# Auxilary.net
KiCad netlist of a schematic drawn in Altium Designer
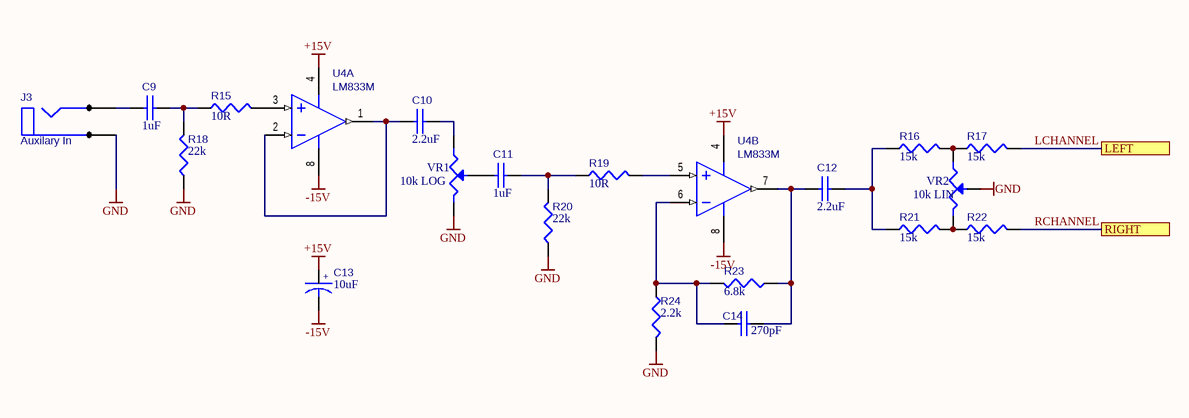
[diagram p0: Auxilary.SchDoc]

(export (version "E")
  (design (tool "Eeschema 10.0.6"))
  (components
    (comp (ref "C9")
      (value "1uF")
      (footprint "RB.2/.4-NP")
      (description "Capacitor")
      (libsource (lib "*") (part "CAP"))
    )
    (comp (ref "C10")
      (value "2.2uF")
      (footprint "RB.2/.4-NP")
      (description "Capacitor")
      (libsource (lib "*") (part "CAP"))
    )
    (comp (ref "C11")
      (value "1uF")
      (footprint "RB.2/.4-NP")
      (description "Capacitor")
      (libsource (lib "*") (part "CAP"))
    )
    (comp (ref "C12")
      (value "2.2uF")
      (footprint "RB.2/.4-NP")
      (description "Capacitor")
      (libsource (lib "*") (part "CAP"))
    )
    (comp (ref "C13")
      (value "10uF")
      (footprint "RB.2/.4")
      (description "Bi-Polar Capacitor")
      (libsource (lib "*") (part "CAPACITOR POL"))
    )
    (comp (ref "C14")
      (value "270pF")
      (footprint "RAD0.2")
      (description "Capacitor")
      (libsource (lib "*") (part "CAP"))
    )
    (comp (ref "J3")
      (value "Auxilary In")
      (footprint "JACK-6.25MM")
      (libsource (lib "*") (part "PHONEJACK MONO"))
    )
    (comp (ref "R15")
      (value "10R")
      (footprint "AXIAL0.4")
      (description "Resistor")
      (libsource (lib "") (part "RES1_1"))
    )
    (comp (ref "R16")
      (value "15k")
      (footprint "AXIAL0.4")
      (description "Resistor")
      (libsource (lib "") (part "RES1_1"))
    )
    (comp (ref "R17")
      (value "15k")
      (footprint "AXIAL0.4")
      (description "Resistor")
      (libsource (lib "") (part "RES1_1"))
    )
    (comp (ref "R18")
      (value "22k")
      (footprint "AXIAL0.4")
      (description "Resistor")
      (libsource (lib "") (part "RES1_2"))
    )
    (comp (ref "R19")
      (value "10R")
      (footprint "AXIAL0.4")
      (description "Resistor")
      (libsource (lib "") (part "RES1_1"))
    )
    (comp (ref "R20")
      (value "22k")
      (footprint "AXIAL0.4")
      (description "Resistor")
      (libsource (lib "") (part "RES1_2"))
    )
    (comp (ref "R21")
      (value "15k")
      (footprint "AXIAL0.4")
      (description "Resistor")
      (libsource (lib "") (part "RES1_1"))
    )
    (comp (ref "R22")
      (value "15k")
      (footprint "AXIAL0.4")
      (description "Resistor")
      (libsource (lib "") (part "RES1_1"))
    )
    (comp (ref "R23")
      (value "6.8k")
      (footprint "AXIAL0.4")
      (description "Resistor")
      (libsource (lib "*") (part "RES1"))
    )
    (comp (ref "R24")
      (value "2.2k")
      (footprint "AXIAL0.4")
      (description "Resistor")
      (libsource (lib "") (part "RES1_3"))
    )
    (comp (ref "U4")
      (value "LM833M")
      (footprint "DIP8")
      (description "Fast Settling Dual Operational Amplifier")
      (libsource (lib "*") (part "LM833M"))
    )
    (comp (ref "VR1")
      (value "10k LOG")
      (footprint "POT - 24MM")
      (description "Potentiometer")
      (libsource (lib "*") (part "POT1"))
    )
    (comp (ref "VR2")
      (value "10k LIN")
      (footprint "POT - 24MM")
      (description "Potentiometer")
      (libsource (lib "*") (part "POT1"))
    )
  )
  (nets
    (net (code "1") (name "+15V") (class "Default")
      (node (ref "C13") (pin "1") (pinfunction "1_1") (pintype "passive"))
      (node (ref "U4") (pin "4") (pinfunction "V-_4") (pintype "power_in"))
    )
    (net (code "2") (name "-15V") (class "Default")
      (node (ref "C13") (pin "2") (pinfunction "2_2") (pintype "passive"))
      (node (ref "U4") (pin "8") (pinfunction "V+_8") (pintype "power_in"))
    )
    (net (code "3") (name "/LCHANNEL") (class "Default")
      (node (ref "R17") (pin "2") (pinfunction "2_2") (pintype "passive"))
    )
    (net (code "4") (name "/RCHANNEL") (class "Default")
      (node (ref "R22") (pin "2") (pinfunction "2_2") (pintype "passive"))
    )
    (net (code "5") (name "GND") (class "Default")
      (node (ref "J3") (pin "3") (pinfunction "C_3") (pintype "passive"))
      (node (ref "R18") (pin "1") (pinfunction "1_1") (pintype "passive"))
      (node (ref "R20") (pin "1") (pinfunction "1_1") (pintype "passive"))
      (node (ref "R24") (pin "2") (pinfunction "2_2") (pintype "passive"))
      (node (ref "VR1") (pin "3") (pinfunction "3_3") (pintype "passive"))
      (node (ref "VR2") (pin "2") (pinfunction "W_2") (pintype "passive"))
    )
    (net (code "6") (name "Net-(C9-Pad2)") (class "Default")
      (node (ref "C9") (pin "2") (pinfunction "2_2") (pintype "passive"))
      (node (ref "R15") (pin "1") (pinfunction "1_1") (pintype "passive"))
      (node (ref "R18") (pin "2") (pinfunction "2_2") (pintype "passive"))
    )
    (net (code "7") (name "Net-(C10-Pad2)") (class "Default")
      (node (ref "C10") (pin "2") (pinfunction "2_2") (pintype "passive"))
      (node (ref "VR1") (pin "1") (pinfunction "1_1") (pintype "passive"))
    )
    (net (code "8") (name "Net-(C11-Pad2)") (class "Default")
      (node (ref "C11") (pin "2") (pinfunction "2_2") (pintype "passive"))
      (node (ref "R19") (pin "1") (pinfunction "1_1") (pintype "passive"))
      (node (ref "R20") (pin "2") (pinfunction "2_2") (pintype "passive"))
    )
    (net (code "9") (name "Net-(C12-Pad2)") (class "Default")
      (node (ref "C12") (pin "2") (pinfunction "2_2") (pintype "passive"))
      (node (ref "R16") (pin "1") (pinfunction "1_1") (pintype "passive"))
      (node (ref "R21") (pin "1") (pinfunction "1_1") (pintype "passive"))
    )
    (net (code "10") (name "Net-(J3-A)") (class "Default")
      (node (ref "C9") (pin "1") (pinfunction "1_1") (pintype "passive"))
      (node (ref "J3") (pin "1") (pinfunction "A_1") (pintype "passive"))
    )
    (net (code "11") (name "Net-(R16-Pad2)") (class "Default")
      (node (ref "R16") (pin "2") (pinfunction "2_2") (pintype "passive"))
      (node (ref "R17") (pin "1") (pinfunction "1_1") (pintype "passive"))
      (node (ref "VR2") (pin "1") (pinfunction "1_1") (pintype "passive"))
    )
    (net (code "12") (name "Net-(R21-Pad2)") (class "Default")
      (node (ref "R21") (pin "2") (pinfunction "2_2") (pintype "passive"))
      (node (ref "R22") (pin "1") (pinfunction "1_1") (pintype "passive"))
      (node (ref "VR2") (pin "3") (pinfunction "3_3") (pintype "passive"))
    )
    (net (code "13") (name "Net-(U4A-IN1+)") (class "Default")
      (node (ref "R15") (pin "2") (pinfunction "2_2") (pintype "passive"))
      (node (ref "U4") (pin "3") (pinfunction "IN1+_3") (pintype "input"))
    )
    (net (code "14") (name "Net-(U4A-IN1-)") (class "Default")
      (node (ref "C10") (pin "1") (pinfunction "1_1") (pintype "passive"))
      (node (ref "U4") (pin "1") (pinfunction "OUT1_1") (pintype "output"))
      (node (ref "U4") (pin "2") (pinfunction "IN1-_2") (pintype "input"))
    )
    (net (code "15") (name "Net-(U4B-IN2+)") (class "Default")
      (node (ref "R19") (pin "2") (pinfunction "2_2") (pintype "passive"))
      (node (ref "U4") (pin "5") (pinfunction "IN2+_5") (pintype "input"))
    )
    (net (code "16") (name "Net-(U4B-IN2-)") (class "Default")
      (node (ref "C14") (pin "1") (pinfunction "1_1") (pintype "passive"))
      (node (ref "R23") (pin "2") (pinfunction "2_2") (pintype "passive"))
      (node (ref "R24") (pin "1") (pinfunction "1_1") (pintype "passive"))
      (node (ref "U4") (pin "6") (pinfunction "IN2-_6") (pintype "input"))
    )
    (net (code "17") (name "Net-(U4B-OUT2)") (class "Default")
      (node (ref "C12") (pin "1") (pinfunction "1_1") (pintype "passive"))
      (node (ref "C14") (pin "2") (pinfunction "2_2") (pintype "passive"))
      (node (ref "R23") (pin "1") (pinfunction "1_1") (pintype "passive"))
      (node (ref "U4") (pin "7") (pinfunction "OUT2_7") (pintype "output"))
    )
    (net (code "18") (name "Net-(VR1-W)") (class "Default")
      (node (ref "C11") (pin "1") (pinfunction "1_1") (pintype "passive"))
      (node (ref "VR1") (pin "2") (pinfunction "W_2") (pintype "passive"))
    )
  )
)
